# projet_pcb_bluepill_f103.net
KiCad netlist of a schematic drawn in Altium Designer
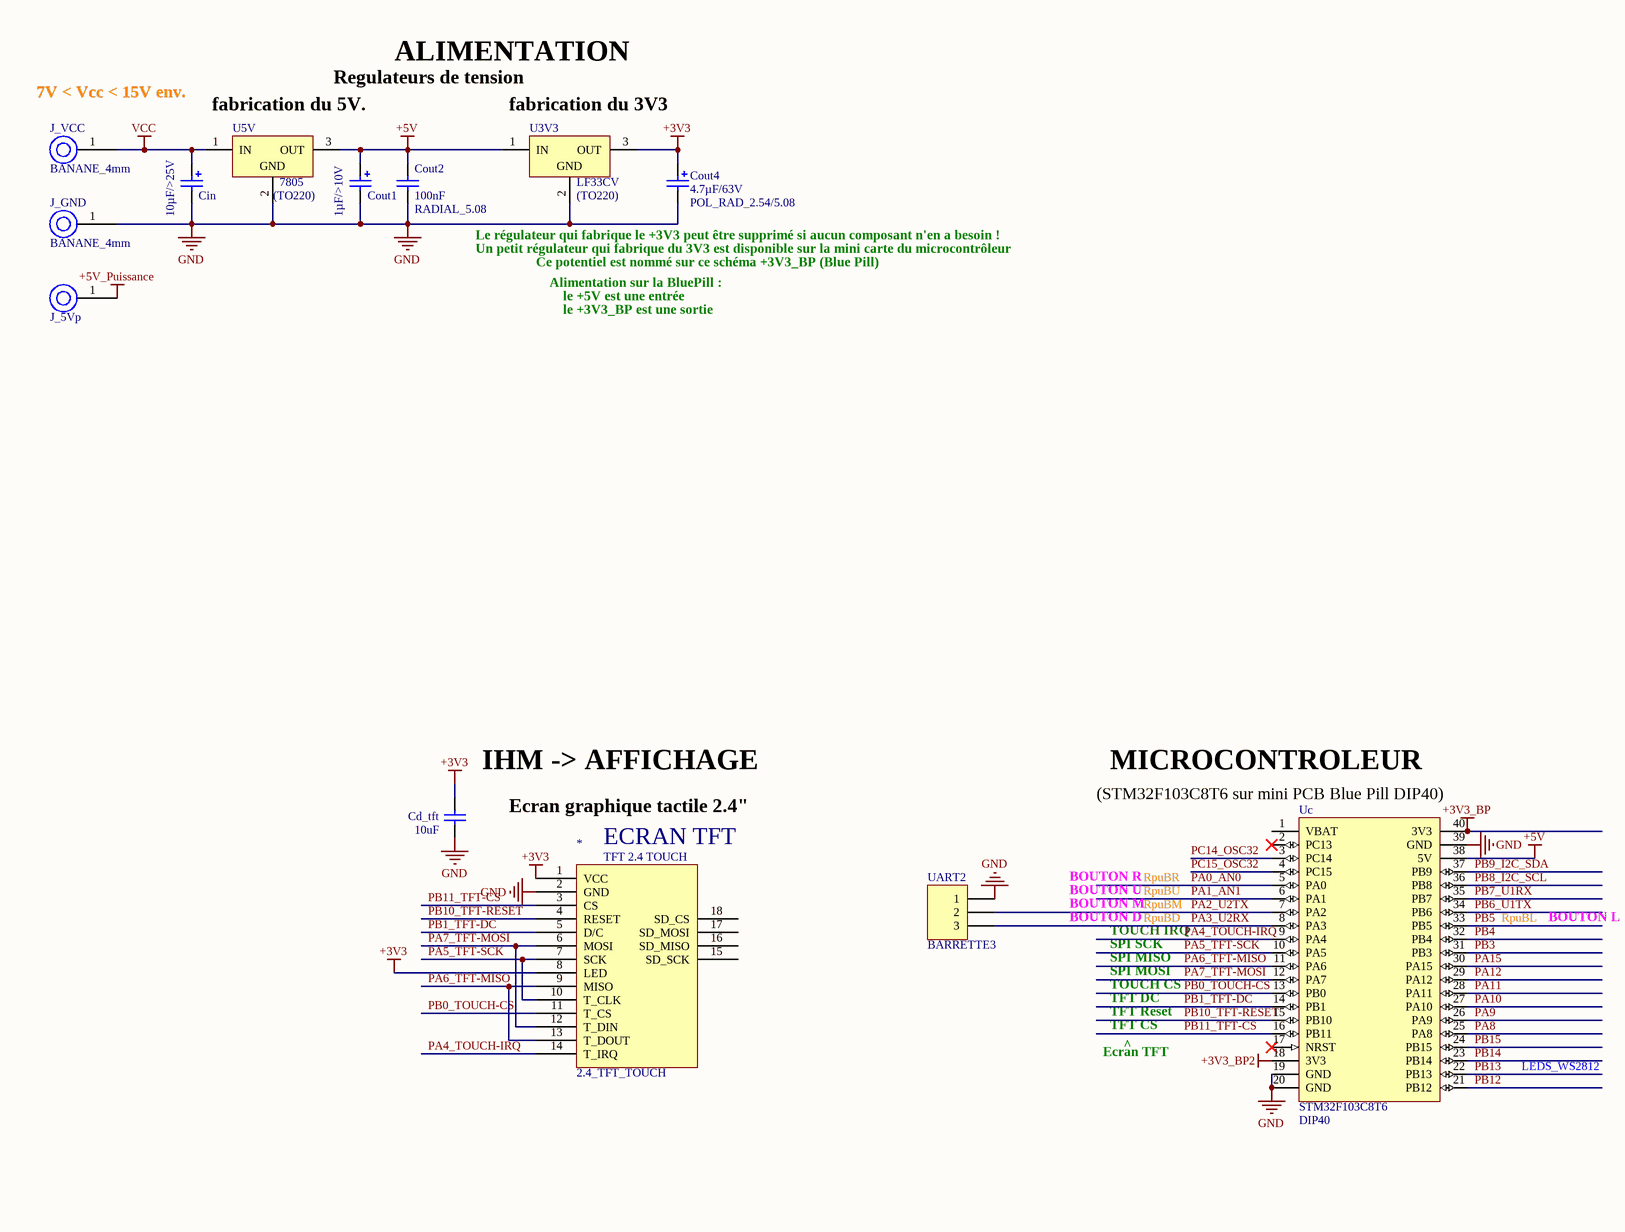
[diagram p0: projet_pcb_bluepill_f103.SchDoc, left]
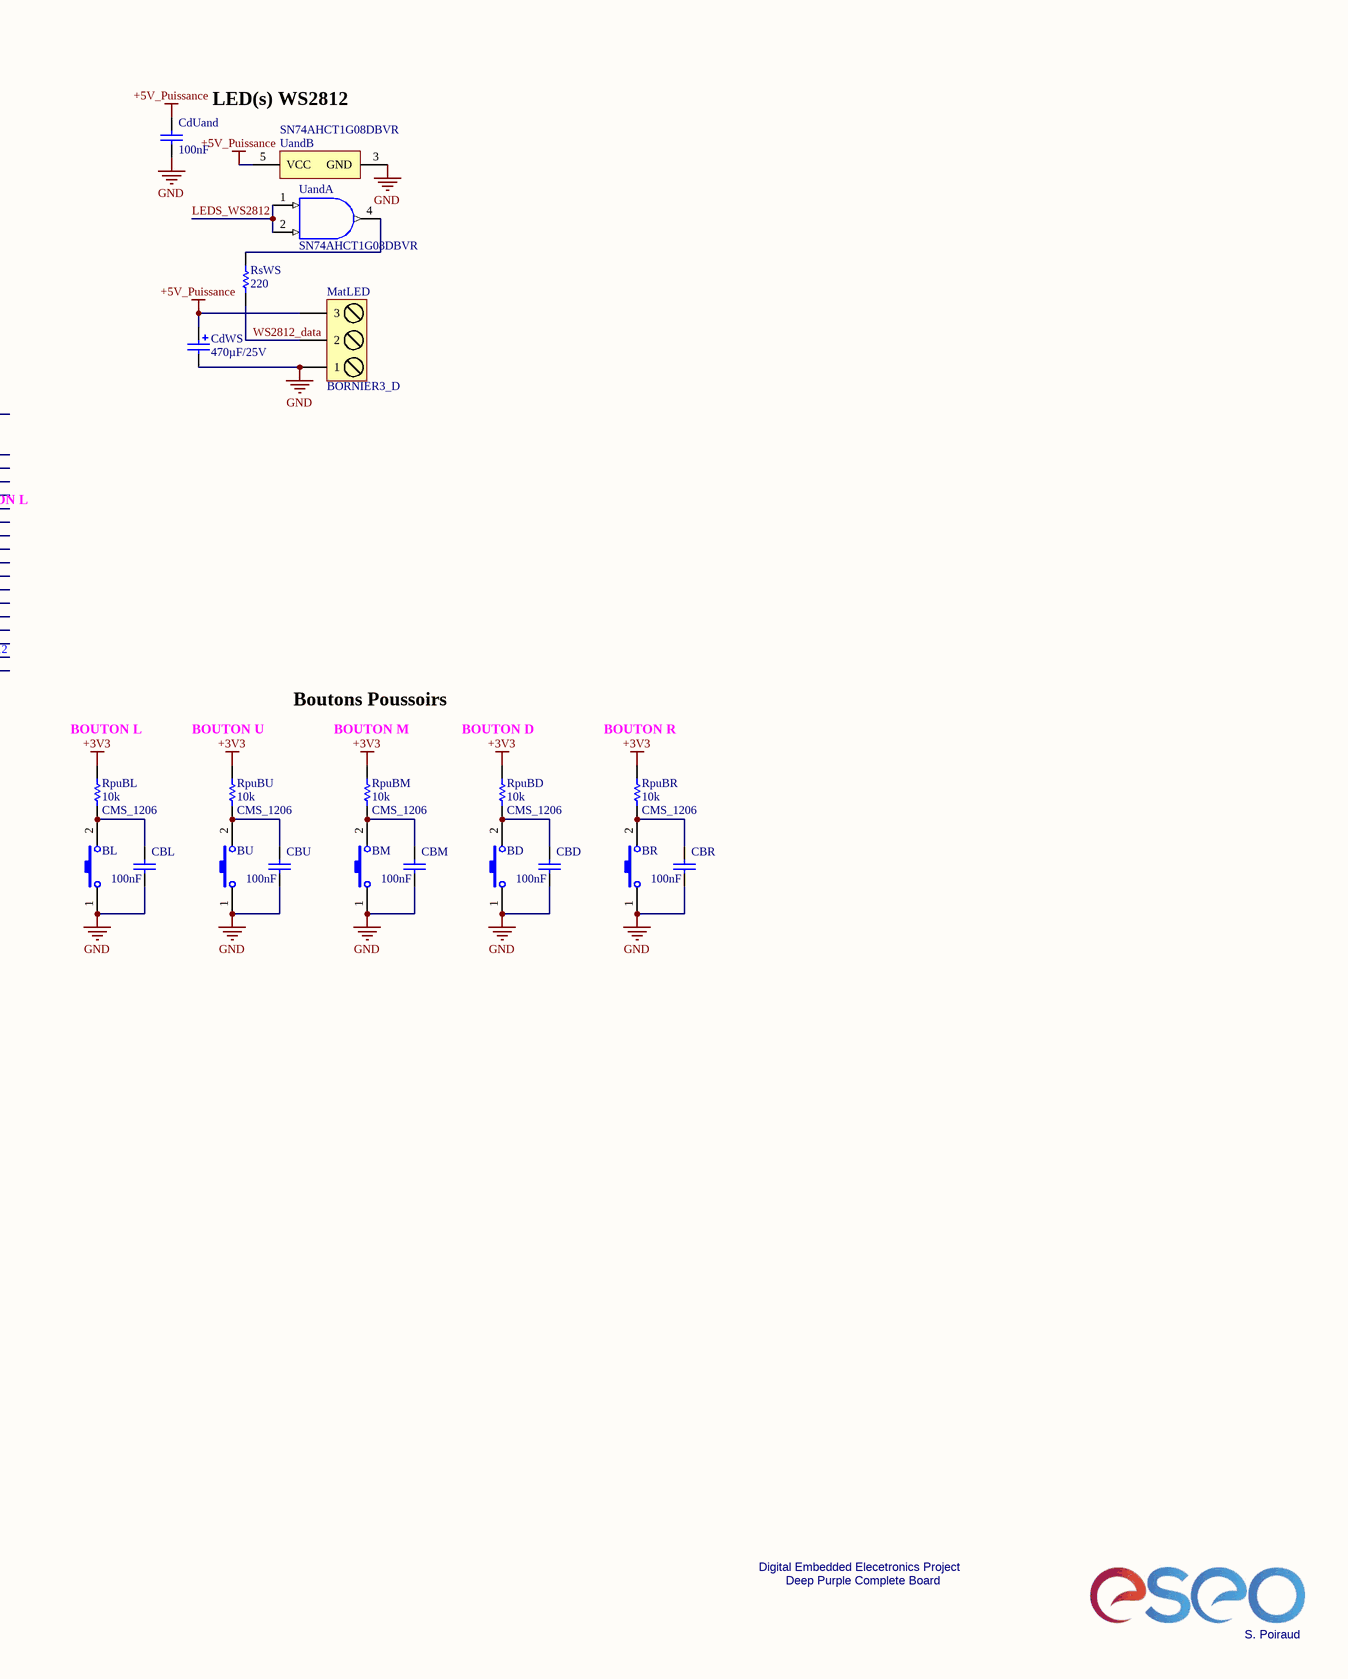
[diagram p1: projet_pcb_bluepill_f103.SchDoc, right]

(export (version "E")
  (design (tool "Eeschema 10.0.6"))
  (components
    (comp (ref "*")
      (value "2.4_TFT_TOUCH")
      (footprint "2.4_TFT_TOUCH")
      (libsource (lib "_ROBOT") (part "2.4_TFT_TOUCH"))
    )
    (comp (ref "BD")
      (value "BOUTON_POUSSOIR_MINIATURE_TRAVERSANT")
      (footprint "BOUTON_POUSSE_PLAT_6x6")
      (description "BOUTON POUSSOIR MINIATURE TRAVERSANT ON/OFF")
      (libsource (lib "commutation") (part "BOUTON_POUSSOIR_MINIATURE_TRAVERSANT"))
    )
    (comp (ref "BL")
      (value "BOUTON_POUSSOIR_MINIATURE_TRAVERSANT")
      (footprint "BOUTON_POUSSE_PLAT_6x6")
      (description "BOUTON POUSSOIR MINIATURE TRAVERSANT ON/OFF")
      (libsource (lib "commutation") (part "BOUTON_POUSSOIR_MINIATURE_TRAVERSANT"))
    )
    (comp (ref "BM")
      (value "BOUTON_POUSSOIR_MINIATURE_TRAVERSANT")
      (footprint "BOUTON_POUSSE_PLAT_6x6")
      (description "BOUTON POUSSOIR MINIATURE TRAVERSANT ON/OFF")
      (libsource (lib "commutation") (part "BOUTON_POUSSOIR_MINIATURE_TRAVERSANT"))
    )
    (comp (ref "BR")
      (value "BOUTON_POUSSOIR_MINIATURE_TRAVERSANT")
      (footprint "BOUTON_POUSSE_PLAT_6x6")
      (description "BOUTON POUSSOIR MINIATURE TRAVERSANT ON/OFF")
      (libsource (lib "commutation") (part "BOUTON_POUSSOIR_MINIATURE_TRAVERSANT"))
    )
    (comp (ref "BU")
      (value "BOUTON_POUSSOIR_MINIATURE_TRAVERSANT")
      (footprint "BOUTON_POUSSE_PLAT_6x6")
      (description "BOUTON POUSSOIR MINIATURE TRAVERSANT ON/OFF")
      (libsource (lib "commutation") (part "BOUTON_POUSSOIR_MINIATURE_TRAVERSANT"))
    )
    (comp (ref "CBD")
      (value "100nF")
      (footprint "C0805_N")
      (fields (field (name "Comment") "Condensateur 0805"))
      (libsource (lib "composants passifs") (part "CONDENSATEUR_CER_RAD_5.08"))
    )
    (comp (ref "CBL")
      (value "100nF")
      (footprint "C0805_N")
      (fields (field (name "Comment") "Condensateur 0805"))
      (libsource (lib "composants passifs") (part "CONDENSATEUR_CER_RAD_5.08"))
    )
    (comp (ref "CBM")
      (value "100nF")
      (footprint "C0805_N")
      (fields (field (name "Comment") "Condensateur 0805"))
      (libsource (lib "composants passifs") (part "CONDENSATEUR_CER_RAD_5.08"))
    )
    (comp (ref "CBR")
      (value "100nF")
      (footprint "C0805_N")
      (fields (field (name "Comment") "Condensateur 0805"))
      (libsource (lib "composants passifs") (part "CONDENSATEUR_CER_RAD_5.08"))
    )
    (comp (ref "CBU")
      (value "100nF")
      (footprint "C0805_N")
      (fields (field (name "Comment") "Condensateur 0805"))
      (libsource (lib "composants passifs") (part "CONDENSATEUR_CER_RAD_5.08"))
    )
    (comp (ref "CdUand")
      (value "100nF")
      (footprint "C0805_N")
      (description "CONDENSATEUR_CER_CMS_0805")
      (fields (field (name "Comment") "CONDENSATEUR_CER_RAD_5.08"))
      (libsource (lib "composants passifs") (part "CONDENSATEUR_CER_RAD_5.08"))
    )
    (comp (ref "CdWS")
      (value "470µF/25V")
      (footprint "CONDENSATEUR_POLARISE_ELECTROLYTIQUE_RADIAL_5.08/10.16")
      (description "CONDENSATEUR POLARISE ELECTROLYTIQUE RADIAL 5.08/10.16")
      (fields (field (name "Comment") "CONDENSATEUR_POL_ELECTROLY_RAD_5.08/10.16"))
      (libsource (lib "composants passifs") (part "CONDENSATEUR_POL_ELECTROLY_RAD_5.08/10.16"))
    )
    (comp (ref "Cd_tft")
      (value "10uF")
      (footprint "CONDENSATEUR_POLARISE_ELECTROLYTIQUE_RADIAL_2.54/5.08")
      (description "Capacitor")
      (fields (field (name "PUBLISHER") "Altium Limited"))
      (libsource (lib "_ROBOT") (part "Condensateur"))
    )
    (comp (ref "Cin")
      (value "10µF/>25V")
      (footprint "CONDENSATEUR_POLARISE_ELECTROLYTIQUE_RADIAL_2.0/5.08")
      (description "CONDENSATEUR POLARISE ELECTROLYTIQUE RADIAL 2.0/5.08")
      (fields (field (name "Comment") "CONDENSATEUR_POL_ELECTROLY_RAD_2.0/5.08"))
      (libsource (lib "composants passifs") (part "CONDENSATEUR_POL_ELECTROLY_RAD_2.0/5.08"))
    )
    (comp (ref "Cout1")
      (value "1µF/>10V")
      (footprint "CONDENSATEUR_POLARISE_ELECTROLYTIQUE_RADIAL_2.0/5.08")
      (description "CONDENSATEUR POLARISE ELECTROLYTIQUE RADIAL 2.0/5.08")
      (fields (field (name "Comment") "CONDENSATEUR_POL_ELECTROLY_RAD_2.0/5.08"))
      (libsource (lib "composants passifs") (part "CONDENSATEUR_POL_ELECTROLY_RAD_2.0/5.08"))
    )
    (comp (ref "Cout2")
      (value "100nF")
      (footprint "CONDENSATEUR_CERAMIQUE_RADIAL_5.08")
      (description "CONDENSATEUR TRAVERSANT CERAMIQUE RADIAL 5.08mm")
      (fields (field (name "TYPE") "RADIAL_5.08") (field (name "Comment") "CONDENSATEUR_CER_RAD_5.08"))
      (libsource (lib "composants passifs") (part "CONDENSATEUR_CER_RAD_5.08"))
    )
    (comp (ref "Cout4")
      (value "4.7µF/63V")
      (footprint "CONDENSATEUR_POLARISE_ELECTROLYTIQUE_RADIAL_2.54/5.08")
      (description "CONDENSATEUR POLARISE ELECTROLYTIQUE RADIAL 2.54/5.08")
      (fields
        (field (name "TYPE") "POL_RAD_2.54/5.08")
        (field (name "Comment") "CONDENSATEUR_POL_ELECTROLY_RAD_2.54/5.08")
      )
      (libsource (lib "composants passifs") (part "CONDENSATEUR_POL_ELECTROLY_RAD_2.54/5.08"))
    )
    (comp (ref "J_5Vp")
      (value "DOUILLE BANANE 4mm")
      (footprint "DOUILLE_BANANE_4mm")
      (description "DOUILLE BANANE 4 mm")
      (libsource (lib "connecteurs") (part "DOUILLE_BANANE_4mm"))
    )
    (comp (ref "J_GND")
      (value "DOUILLE BANANE 4mm")
      (footprint "DOUILLE_BANANE_4mm")
      (description "DOUILLE BANANE 4 mm")
      (fields (field (name "TYPE") "BANANE_4mm"))
      (libsource (lib "connecteurs") (part "DOUILLE_BANANE_4mm"))
    )
    (comp (ref "J_VCC")
      (value "DOUILLE BANANE 4mm")
      (footprint "DOUILLE_BANANE_4mm")
      (description "DOUILLE BANANE 4 mm")
      (fields (field (name "TYPE") "BANANE_4mm"))
      (libsource (lib "connecteurs") (part "DOUILLE_BANANE_4mm"))
    )
    (comp (ref "MatLED")
      (value "BORNIER3 DROIT A VIS")
      (footprint "BORNIER3_A_VIS")
      (description "BORNIER 3 PLOTS DROIT A VIS 5.08mm")
      (fields (field (name "TYPE") "BORNIER3_D"))
      (libsource (lib "connecteurs") (part "BORNIER3_DROIT_A VIS"))
    )
    (comp (ref "RpuBD")
      (value "10k")
      (footprint "RESISTANCE_CMS_1206")
      (description "RESISTANCE CMS 1206")
      (fields (field (name "TYPE") "CMS_1206") (field (name "Comment") "RESISTANCE_CMS_1206"))
      (libsource (lib "composants passifs") (part "RESISTANCE_CMS_1206"))
    )
    (comp (ref "RpuBL")
      (value "10k")
      (footprint "RESISTANCE_CMS_1206")
      (description "RESISTANCE CMS 1206")
      (fields (field (name "TYPE") "CMS_1206") (field (name "Comment") "RESISTANCE_CMS_1206"))
      (libsource (lib "composants passifs") (part "RESISTANCE_CMS_1206"))
    )
    (comp (ref "RpuBM")
      (value "10k")
      (footprint "RESISTANCE_CMS_1206")
      (description "RESISTANCE CMS 1206")
      (fields (field (name "TYPE") "CMS_1206") (field (name "Comment") "RESISTANCE_CMS_1206"))
      (libsource (lib "composants passifs") (part "RESISTANCE_CMS_1206"))
    )
    (comp (ref "RpuBR")
      (value "10k")
      (footprint "RESISTANCE_CMS_1206")
      (description "RESISTANCE CMS 1206")
      (fields (field (name "TYPE") "CMS_1206") (field (name "Comment") "RESISTANCE_CMS_1206"))
      (libsource (lib "composants passifs") (part "RESISTANCE_CMS_1206"))
    )
    (comp (ref "RpuBU")
      (value "10k")
      (footprint "RESISTANCE_CMS_1206")
      (description "RESISTANCE CMS 1206")
      (fields (field (name "TYPE") "CMS_1206") (field (name "Comment") "RESISTANCE_CMS_1206"))
      (libsource (lib "composants passifs") (part "RESISTANCE_CMS_1206"))
    )
    (comp (ref "RsWS")
      (value "220")
      (footprint "R1206_N")
      (description "Resistor")
      (fields (field (name "PUBLISHER") "Altium Limited"))
      (libsource (lib "_ROBOT") (part "Resistor"))
    )
    (comp (ref "U3V3")
      (value "REGULATEUR_TO220_78XX")
      (footprint "REGULATEUR_TO220_78XX")
      (description "REGULATEUR DE TENSION POSITIVE 78XX BOITIER TO220")
      (fields (field (name "TYPE") "LF33CV") (field (name "PACKAGE") "(TO220)"))
      (libsource (lib "composants actifs") (part "REGULATEUR_TO220_78XX"))
    )
    (comp (ref "U5V")
      (value "REGULATEUR_TO220_78XX")
      (footprint "REGULATEUR_TO220_78XX")
      (description "REGULATEUR DE TENSION POSITIVE 78XX BOITIER TO220")
      (fields (field (name "TYPE") "7805") (field (name "PACKAGE") "(TO220)"))
      (libsource (lib "composants actifs") (part "REGULATEUR_TO220_78XX"))
    )
    (comp (ref "Uand")
      (value "SN74AHCT1G08DBVR")
      (footprint "DBV0005A_N")
      (description "Single 2-Input Positive-AND Gate, DBV0005A, LARGE T&R")
      (fields
        (field (name "GENERIC PART NUMBER") "SN74AHCT1G08")
        (field (name "MANUFACTURER") "Texas Instruments")
      )
      (libsource (lib "TI_Logic_Little_Logic") (part "SN74AHCT1G08DBVR"))
    )
    (comp (ref "UART2")
      (value "BARRETTE3")
      (footprint "HDR1X3")
      (description "Header, 3-Pin")
      (fields (field (name "PUBLISHER") "Altium Limited"))
      (libsource (lib "Connecteur") (part "BARRETTE3"))
    )
    (comp (ref "Uc")
      (value "STM32F103C8T6/PCB_DIP40")
      (footprint "STM32F103C8T6_DIP40")
      (fields (field (name "TYPE") "STM32F103C8T6") (field (name "PACKAGE") "DIP40"))
      (libsource (lib "circuits integres") (part "STM32F103C8T6/PCB_DIP40"))
    )
  )
  (nets
    (net (code "1") (name "+3V3") (class "Default")
      (node (ref "*") (pin "1") (pinfunction "VCC_1") (pintype "passive"))
      (node (ref "*") (pin "8") (pinfunction "LED_8") (pintype "passive"))
      (node (ref "Cd_tft") (pin "1") (pinfunction "1_1") (pintype "passive"))
      (node (ref "Cout4") (pin "1") (pinfunction "1_1") (pintype "passive"))
      (node (ref "RpuBD") (pin "2") (pinfunction "2_2") (pintype "passive"))
      (node (ref "RpuBL") (pin "2") (pinfunction "2_2") (pintype "passive"))
      (node (ref "RpuBM") (pin "2") (pinfunction "2_2") (pintype "passive"))
      (node (ref "RpuBR") (pin "2") (pinfunction "2_2") (pintype "passive"))
      (node (ref "RpuBU") (pin "2") (pinfunction "2_2") (pintype "passive"))
      (node (ref "U3V3") (pin "3") (pinfunction "OUT_3") (pintype "power_in"))
    )
    (net (code "2") (name "+3V3_BP") (class "Default")
      (node (ref "Uc") (pin "40") (pinfunction "3V3_40") (pintype "power_in"))
    )
    (net (code "3") (name "+3V3_BP2") (class "Default")
      (node (ref "Uc") (pin "18") (pinfunction "3V3_18") (pintype "power_in"))
    )
    (net (code "4") (name "+5V") (class "Default")
      (node (ref "Cout1") (pin "1") (pinfunction "1_1") (pintype "passive"))
      (node (ref "Cout2") (pin "2") (pinfunction "2_2") (pintype "passive"))
      (node (ref "U3V3") (pin "1") (pinfunction "IN_1") (pintype "power_in"))
      (node (ref "U5V") (pin "3") (pinfunction "OUT_3") (pintype "power_in"))
      (node (ref "Uc") (pin "38") (pinfunction "5V_38") (pintype "power_in"))
    )
    (net (code "5") (name "+5V_Puissance") (class "Default")
      (node (ref "CdUand") (pin "2") (pinfunction "2_2") (pintype "passive"))
      (node (ref "CdWS") (pin "1") (pinfunction "1_1") (pintype "passive"))
      (node (ref "J_5Vp") (pin "1") (pinfunction "1_1") (pintype "passive"))
      (node (ref "MatLED") (pin "3") (pinfunction "3_3") (pintype "passive"))
      (node (ref "Uand") (pin "5") (pinfunction "VCC_5") (pintype "power_in"))
    )
    (net (code "6") (name "/LEDS_WS2812") (class "Default")
      (node (ref "Uand") (pin "1") (pinfunction "A_1") (pintype "input"))
      (node (ref "Uand") (pin "2") (pinfunction "B_2") (pintype "input"))
      (node (ref "Uc") (pin "22") (pinfunction "PB13_22") (pintype "bidirectional"))
    )
    (net (code "7") (name "/PA0_AN0") (class "Default")
      (node (ref "Uc") (pin "5") (pinfunction "PA0_5") (pintype "bidirectional"))
    )
    (net (code "8") (name "/PA1_AN1") (class "Default")
      (node (ref "Uc") (pin "6") (pinfunction "PA1_6") (pintype "bidirectional"))
    )
    (net (code "9") (name "/PA2_U2TX") (class "Default")
      (node (ref "UART2") (pin "2") (pinfunction "2_2") (pintype "passive"))
      (node (ref "Uc") (pin "7") (pinfunction "PA2_7") (pintype "bidirectional"))
    )
    (net (code "10") (name "/PA3_U2RX") (class "Default")
      (node (ref "UART2") (pin "3") (pinfunction "3_3") (pintype "passive"))
      (node (ref "Uc") (pin "8") (pinfunction "PA3_8") (pintype "bidirectional"))
    )
    (net (code "11") (name "/PA4_TOUCH-IRQ") (class "Default")
      (node (ref "*") (pin "14") (pinfunction "T_IRQ_14") (pintype "passive"))
      (node (ref "Uc") (pin "9") (pinfunction "PA4_9") (pintype "bidirectional"))
    )
    (net (code "12") (name "/PA5_TFT-SCK") (class "Default")
      (node (ref "*") (pin "10") (pinfunction "T_CLK_10") (pintype "passive"))
      (node (ref "*") (pin "7") (pinfunction "SCK_7") (pintype "passive"))
      (node (ref "Uc") (pin "10") (pinfunction "PA5_10") (pintype "bidirectional"))
    )
    (net (code "13") (name "/PA6_TFT-MISO") (class "Default")
      (node (ref "*") (pin "13") (pinfunction "T_DOUT_13") (pintype "passive"))
      (node (ref "*") (pin "9") (pinfunction "MISO_9") (pintype "passive"))
      (node (ref "Uc") (pin "11") (pinfunction "PA6_11") (pintype "bidirectional"))
    )
    (net (code "14") (name "/PA7_TFT-MOSI") (class "Default")
      (node (ref "*") (pin "12") (pinfunction "T_DIN_12") (pintype "passive"))
      (node (ref "*") (pin "6") (pinfunction "MOSI_6") (pintype "passive"))
      (node (ref "Uc") (pin "12") (pinfunction "PA7_12") (pintype "bidirectional"))
    )
    (net (code "15") (name "/PA8") (class "Default")
      (node (ref "Uc") (pin "25") (pinfunction "PA8_25") (pintype "bidirectional"))
    )
    (net (code "16") (name "/PA9") (class "Default")
      (node (ref "Uc") (pin "26") (pinfunction "PA9_26") (pintype "bidirectional"))
    )
    (net (code "17") (name "/PA10") (class "Default")
      (node (ref "Uc") (pin "27") (pinfunction "PA10_27") (pintype "bidirectional"))
    )
    (net (code "18") (name "/PA11") (class "Default")
      (node (ref "Uc") (pin "28") (pinfunction "PA11_28") (pintype "bidirectional"))
    )
    (net (code "19") (name "/PA12") (class "Default")
      (node (ref "Uc") (pin "29") (pinfunction "PA12_29") (pintype "bidirectional"))
    )
    (net (code "20") (name "/PA15") (class "Default")
      (node (ref "Uc") (pin "30") (pinfunction "PA15_30") (pintype "bidirectional"))
    )
    (net (code "21") (name "/PB0_TOUCH-CS") (class "Default")
      (node (ref "*") (pin "11") (pinfunction "T_CS_11") (pintype "passive"))
      (node (ref "Uc") (pin "13") (pinfunction "PB0_13") (pintype "bidirectional"))
    )
    (net (code "22") (name "/PB1_TFT-DC") (class "Default")
      (node (ref "*") (pin "5") (pinfunction "D/C_5") (pintype "passive"))
      (node (ref "Uc") (pin "14") (pinfunction "PB1_14") (pintype "bidirectional"))
    )
    (net (code "23") (name "/PB3") (class "Default")
      (node (ref "Uc") (pin "31") (pinfunction "PB3_31") (pintype "bidirectional"))
    )
    (net (code "24") (name "/PB4") (class "Default")
      (node (ref "Uc") (pin "32") (pinfunction "PB4_32") (pintype "bidirectional"))
    )
    (net (code "25") (name "/PB5") (class "Default")
      (node (ref "Uc") (pin "33") (pinfunction "PB5_33") (pintype "bidirectional"))
    )
    (net (code "26") (name "/PB6_U1TX") (class "Default")
      (node (ref "Uc") (pin "34") (pinfunction "PB6_34") (pintype "bidirectional"))
    )
    (net (code "27") (name "/PB7_U1RX") (class "Default")
      (node (ref "Uc") (pin "35") (pinfunction "PB7_35") (pintype "bidirectional"))
    )
    (net (code "28") (name "/PB8_I2C_SCL") (class "Default")
      (node (ref "Uc") (pin "36") (pinfunction "PB8_36") (pintype "bidirectional"))
    )
    (net (code "29") (name "/PB9_I2C_SDA") (class "Default")
      (node (ref "Uc") (pin "37") (pinfunction "PB9_37") (pintype "bidirectional"))
    )
    (net (code "30") (name "/PB10_TFT-RESET") (class "Default")
      (node (ref "*") (pin "4") (pinfunction "RESET_4") (pintype "passive"))
      (node (ref "Uc") (pin "15") (pinfunction "PB10_15") (pintype "bidirectional"))
    )
    (net (code "31") (name "/PB11_TFT-CS") (class "Default")
      (node (ref "*") (pin "3") (pinfunction "CS_3") (pintype "passive"))
      (node (ref "Uc") (pin "16") (pinfunction "PB11_16") (pintype "bidirectional"))
    )
    (net (code "32") (name "/PB12") (class "Default")
      (node (ref "Uc") (pin "21") (pinfunction "PB12_21") (pintype "bidirectional"))
    )
    (net (code "33") (name "/PB14") (class "Default")
      (node (ref "Uc") (pin "23") (pinfunction "PB14_23") (pintype "bidirectional"))
    )
    (net (code "34") (name "/PB15") (class "Default")
      (node (ref "Uc") (pin "24") (pinfunction "PB15_24") (pintype "bidirectional"))
    )
    (net (code "35") (name "/PC14_OSC32") (class "Default")
      (node (ref "Uc") (pin "3") (pinfunction "PC14_3") (pintype "bidirectional"))
    )
    (net (code "36") (name "/PC15_OSC32") (class "Default")
      (node (ref "Uc") (pin "4") (pinfunction "PC15_4") (pintype "bidirectional"))
    )
    (net (code "37") (name "/WS2812_data") (class "Default")
      (node (ref "MatLED") (pin "2") (pinfunction "2_2") (pintype "passive"))
      (node (ref "RsWS") (pin "1") (pinfunction "1_1") (pintype "passive"))
    )
    (net (code "38") (name "GND") (class "Default")
      (node (ref "*") (pin "2") (pinfunction "GND_2") (pintype "passive"))
      (node (ref "BD") (pin "1") (pinfunction "1_1") (pintype "passive"))
      (node (ref "BL") (pin "1") (pinfunction "1_1") (pintype "passive"))
      (node (ref "BM") (pin "1") (pinfunction "1_1") (pintype "passive"))
      (node (ref "BR") (pin "1") (pinfunction "1_1") (pintype "passive"))
      (node (ref "BU") (pin "1") (pinfunction "1_1") (pintype "passive"))
      (node (ref "CBD") (pin "1") (pinfunction "1_1") (pintype "passive"))
      (node (ref "CBL") (pin "1") (pinfunction "1_1") (pintype "passive"))
      (node (ref "CBM") (pin "1") (pinfunction "1_1") (pintype "passive"))
      (node (ref "CBR") (pin "1") (pinfunction "1_1") (pintype "passive"))
      (node (ref "CBU") (pin "1") (pinfunction "1_1") (pintype "passive"))
      (node (ref "CdUand") (pin "1") (pinfunction "1_1") (pintype "passive"))
      (node (ref "CdWS") (pin "2") (pinfunction "2_2") (pintype "passive"))
      (node (ref "Cd_tft") (pin "2") (pinfunction "2_2") (pintype "passive"))
      (node (ref "Cin") (pin "2") (pinfunction "2_2") (pintype "passive"))
      (node (ref "Cout1") (pin "2") (pinfunction "2_2") (pintype "passive"))
      (node (ref "Cout2") (pin "1") (pinfunction "1_1") (pintype "passive"))
      (node (ref "Cout4") (pin "2") (pinfunction "2_2") (pintype "passive"))
      (node (ref "J_GND") (pin "1") (pinfunction "1_1") (pintype "passive"))
      (node (ref "MatLED") (pin "1") (pinfunction "1_1") (pintype "passive"))
      (node (ref "U3V3") (pin "2") (pinfunction "GND_2") (pintype "power_in"))
      (node (ref "U5V") (pin "2") (pinfunction "GND_2") (pintype "power_in"))
      (node (ref "UART2") (pin "1") (pinfunction "1_1") (pintype "passive"))
      (node (ref "Uand") (pin "3") (pinfunction "GND_3") (pintype "power_in"))
      (node (ref "Uc") (pin "19") (pinfunction "GND_19") (pintype "power_in"))
      (node (ref "Uc") (pin "20") (pinfunction "GND_20") (pintype "power_in"))
      (node (ref "Uc") (pin "39") (pinfunction "GND_39") (pintype "power_in"))
    )
    (net (code "39") (name "Net-(BD-Pad2)") (class "Default")
      (node (ref "BD") (pin "2") (pinfunction "2_2") (pintype "passive"))
      (node (ref "CBD") (pin "2") (pinfunction "2_2") (pintype "passive"))
      (node (ref "RpuBD") (pin "1") (pinfunction "1_1") (pintype "passive"))
    )
    (net (code "40") (name "Net-(BL-Pad2)") (class "Default")
      (node (ref "BL") (pin "2") (pinfunction "2_2") (pintype "passive"))
      (node (ref "CBL") (pin "2") (pinfunction "2_2") (pintype "passive"))
      (node (ref "RpuBL") (pin "1") (pinfunction "1_1") (pintype "passive"))
    )
    (net (code "41") (name "Net-(BM-Pad2)") (class "Default")
      (node (ref "BM") (pin "2") (pinfunction "2_2") (pintype "passive"))
      (node (ref "CBM") (pin "2") (pinfunction "2_2") (pintype "passive"))
      (node (ref "RpuBM") (pin "1") (pinfunction "1_1") (pintype "passive"))
    )
    (net (code "42") (name "Net-(BR-Pad2)") (class "Default")
      (node (ref "BR") (pin "2") (pinfunction "2_2") (pintype "passive"))
      (node (ref "CBR") (pin "2") (pinfunction "2_2") (pintype "passive"))
      (node (ref "RpuBR") (pin "1") (pinfunction "1_1") (pintype "passive"))
    )
    (net (code "43") (name "Net-(BU-Pad2)") (class "Default")
      (node (ref "BU") (pin "2") (pinfunction "2_2") (pintype "passive"))
      (node (ref "CBU") (pin "2") (pinfunction "2_2") (pintype "passive"))
      (node (ref "RpuBU") (pin "1") (pinfunction "1_1") (pintype "passive"))
    )
    (net (code "44") (name "Net-(UandA-Y)") (class "Default")
      (node (ref "RsWS") (pin "2") (pinfunction "2_2") (pintype "passive"))
      (node (ref "Uand") (pin "4") (pinfunction "Y_4") (pintype "output"))
    )
    (net (code "45") (name "VCC") (class "Default")
      (node (ref "Cin") (pin "1") (pinfunction "1_1") (pintype "passive"))
      (node (ref "J_VCC") (pin "1") (pinfunction "1_1") (pintype "passive"))
      (node (ref "U5V") (pin "1") (pinfunction "IN_1") (pintype "power_in"))
    )
    (net (code "46") (name "unconnected-(*-SD_CS-Pad18)") (class "Default")
      (node (ref "*") (pin "18") (pinfunction "SD_CS_18") (pintype "passive"))
    )
    (net (code "47") (name "unconnected-(*-SD_MISO-Pad16)") (class "Default")
      (node (ref "*") (pin "16") (pinfunction "SD_MISO_16") (pintype "passive"))
    )
    (net (code "48") (name "unconnected-(*-SD_MOSI-Pad17)") (class "Default")
      (node (ref "*") (pin "17") (pinfunction "SD_MOSI_17") (pintype "passive"))
    )
    (net (code "49") (name "unconnected-(*-SD_SCK-Pad15)") (class "Default")
      (node (ref "*") (pin "15") (pinfunction "SD_SCK_15") (pintype "passive"))
    )
    (net (code "50") (name "unconnected-(Uc-NRST-Pad17)") (class "Default")
      (node (ref "Uc") (pin "17") (pinfunction "NRST_17") (pintype "input+no_connect"))
    )
    (net (code "51") (name "unconnected-(Uc-PC13-Pad2)") (class "Default")
      (node (ref "Uc") (pin "2") (pinfunction "PC13_2") (pintype "bidirectional+no_connect"))
    )
    (net (code "52") (name "unconnected-(Uc-VBAT-Pad1)") (class "Default")
      (node (ref "Uc") (pin "1") (pinfunction "VBAT_1") (pintype "power_in"))
    )
  )
)
